# ATTint_SOMO-4D.net
KiCad netlist of a schematic drawn in EAGLE
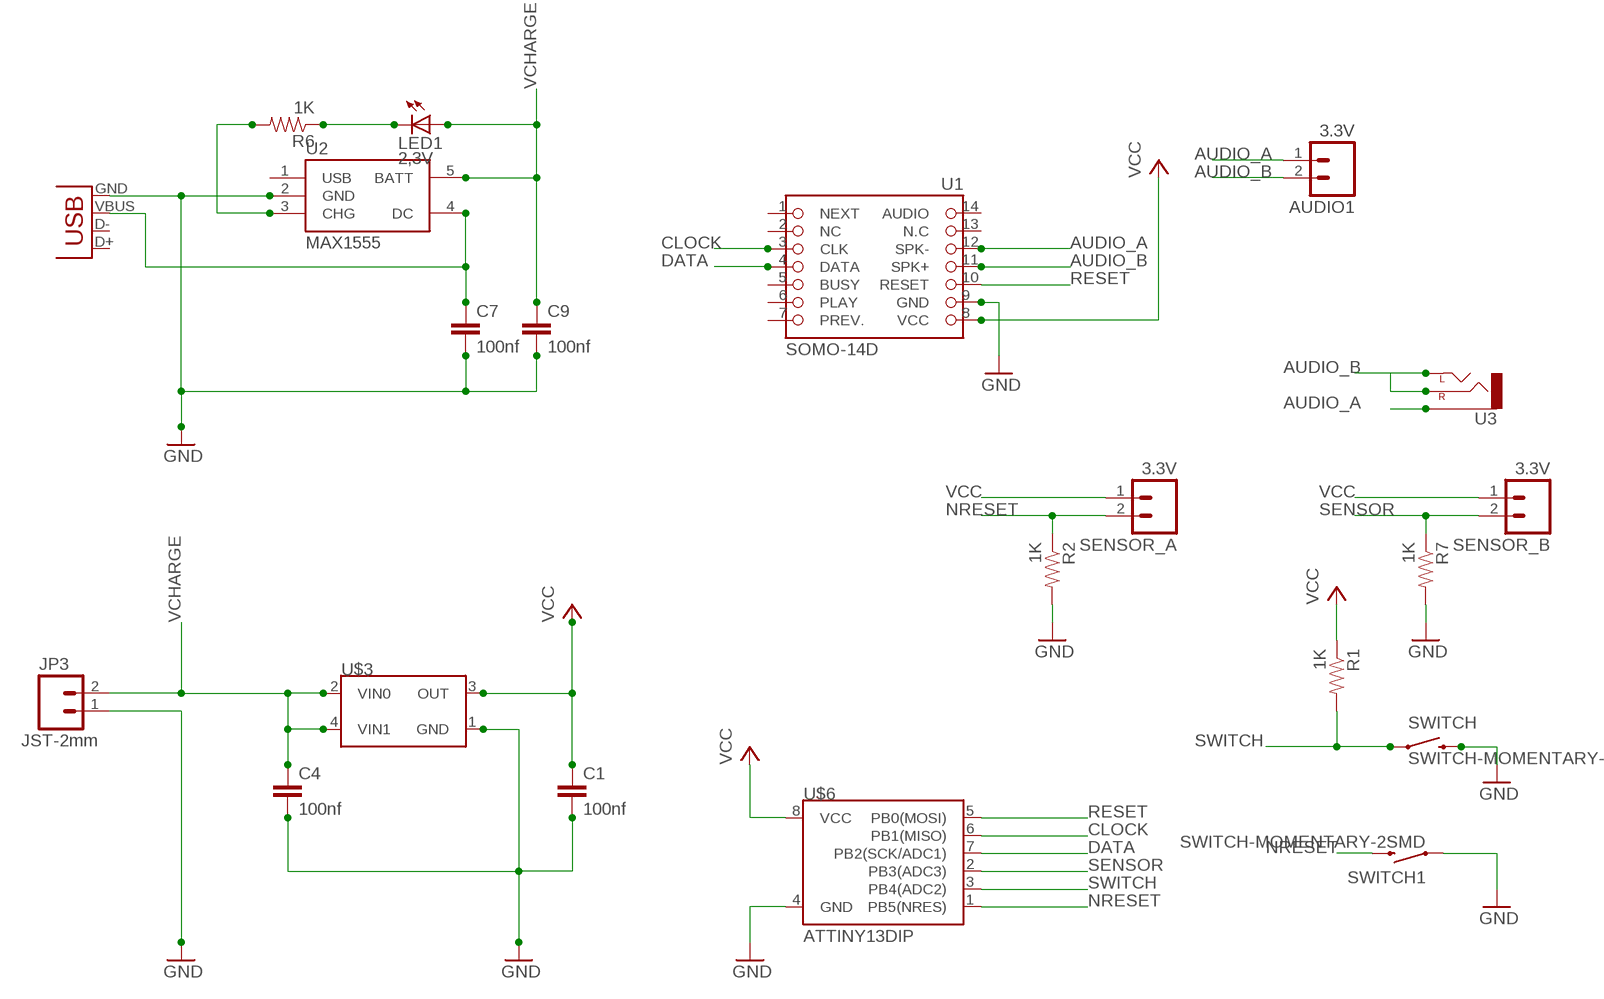
[diagram p0: schematic, sheet 1]

(export (version "E")
  (design (tool "Eeschema 10.0.6"))
  (components
    (comp (ref "AUDIO1")
      (value "3.3V")
      (footprint "eagle-import:1X02_LOCK_LONGPADS")
      (libsource (lib "eagle-import") (part "M02LOCK_LONGPADS"))
    )
    (comp (ref "C1")
      (value "100nf")
      (footprint "eagle-import:0805")
      (libsource (lib "eagle-import") (part "CAP0805"))
    )
    (comp (ref "C4")
      (value "100nf")
      (footprint "eagle-import:0805")
      (libsource (lib "eagle-import") (part "CAP0805"))
    )
    (comp (ref "C7")
      (value "100nf")
      (footprint "eagle-import:0805")
      (libsource (lib "eagle-import") (part "CAP0805"))
    )
    (comp (ref "C9")
      (value "100nf")
      (footprint "eagle-import:0805")
      (libsource (lib "eagle-import") (part "CAP0805"))
    )
    (comp (ref "JP3")
      (value "JST-2mm")
      (footprint "eagle-import:JST-2-SMD")
      (libsource (lib "eagle-import") (part "M02-JST-2MM-SMT"))
    )
    (comp (ref "LED1")
      (value "2,3V")
      (footprint "eagle-import:CHIP-LED0805")
      (libsource (lib "eagle-import") (part "LEDCHIP-LED0805"))
    )
    (comp (ref "R1")
      (value "1K")
      (footprint "eagle-import:0805")
      (libsource (lib "eagle-import") (part "RESISTOR"))
    )
    (comp (ref "R2")
      (value "1K")
      (footprint "eagle-import:0805")
      (libsource (lib "eagle-import") (part "RESISTOR"))
    )
    (comp (ref "R6")
      (value "1K")
      (footprint "eagle-import:0805")
      (libsource (lib "eagle-import") (part "RESISTOR"))
    )
    (comp (ref "R7")
      (value "1K")
      (footprint "eagle-import:0805")
      (libsource (lib "eagle-import") (part "RESISTOR"))
    )
    (comp (ref "SENSOR_A")
      (value "3.3V")
      (footprint "eagle-import:1X02_LOCK_LONGPADS")
      (libsource (lib "eagle-import") (part "charles_M02LOCK_LONGPADS"))
    )
    (comp (ref "SENSOR_B")
      (value "3.3V")
      (footprint "eagle-import:1X02_LOCK_LONGPADS")
      (libsource (lib "eagle-import") (part "charles_M02LOCK_LONGPADS"))
    )
    (comp (ref "SWITCH")
      (value "SWITCH-MOMENTARY-2")
      (footprint "eagle-import:TACTILE_SWITCH_TALL")
      (libsource (lib "eagle-import") (part "SWITCH-MOMENTARY-2"))
    )
    (comp (ref "SWITCH1")
      (value "SWITCH-MOMENTARY-2SMD")
      (footprint "eagle-import:TACTILE_SWITCH_SMD")
      (libsource (lib "eagle-import") (part "SWITCH-MOMENTARY-2SMD"))
    )
    (comp (ref "U$3")
      (value "MCP1703")
      (footprint "eagle-import:SOT-89")
      (libsource (lib "eagle-import") (part "MCP1703"))
    )
    (comp (ref "U$6")
      (value "ATTINY13DIP")
      (footprint "eagle-import:DIP08")
      (libsource (lib "eagle-import") (part "ATTINY13DIP"))
    )
    (comp (ref "U1")
      (value "SOMO-14D")
      (footprint "eagle-import:SOMO-14D")
      (libsource (lib "eagle-import") (part "SOMO-14D"))
    )
    (comp (ref "U2")
      (value "MAX1555")
      (footprint "eagle-import:SOT23-5")
      (libsource (lib "eagle-import") (part "MAX1555"))
    )
    (comp (ref "U3")
      (value "AUDIO-JACKSMD2")
      (footprint "eagle-import:AUDIO-JACK-3.5MM-SMD")
      (libsource (lib "eagle-import") (part "AUDIO-JACKSMD2"))
    )
    (comp (ref "X3")
      (value "USB-SMD-NS")
      (footprint "eagle-import:USB-MINIB-NOSTOP")
      (libsource (lib "eagle-import") (part "USB-SMD-NS"))
    )
  )
  (nets
    (net (code "1") (name "/AUDIO_A") (class "Default")
      (node (ref "AUDIO1") (pin "1") (pinfunction "1_1") (pintype "passive"))
      (node (ref "U1") (pin "12") (pinfunction "SPK-_12") (pintype "output"))
      (node (ref "U3") (pin "SLEEVE") (pinfunction "SLEEVE_SLEEVE") (pintype "bidirectional"))
    )
    (net (code "2") (name "/AUDIO_B") (class "Default")
      (node (ref "AUDIO1") (pin "2") (pinfunction "2_2") (pintype "passive"))
      (node (ref "U1") (pin "11") (pinfunction "SPK+_11") (pintype "output"))
      (node (ref "U3") (pin "RING") (pinfunction "RIGHT_RING") (pintype "bidirectional"))
      (node (ref "U3") (pin "TIP") (pinfunction "LEFT_TIP") (pintype "bidirectional"))
    )
    (net (code "3") (name "/CLOCK") (class "Default")
      (node (ref "U$6") (pin "6") (pinfunction "PB1(MISO)_6") (pintype "bidirectional"))
      (node (ref "U1") (pin "3") (pinfunction "CLK_3") (pintype "input"))
    )
    (net (code "4") (name "/DATA") (class "Default")
      (node (ref "U$6") (pin "7") (pinfunction "PB2(SCK/ADC1)_7") (pintype "bidirectional"))
      (node (ref "U1") (pin "4") (pinfunction "DATA_4") (pintype "input"))
    )
    (net (code "5") (name "/NRESET") (class "Default")
      (node (ref "R2") (pin "1") (pinfunction "1_1") (pintype "passive"))
      (node (ref "SENSOR_A") (pin "2") (pinfunction "2_2") (pintype "passive"))
      (node (ref "SWITCH1") (pin "3") (pinfunction "2_3") (pintype "passive"))
      (node (ref "U$6") (pin "1") (pinfunction "PB5(NRES)_1") (pintype "bidirectional"))
    )
    (net (code "6") (name "/RESET") (class "Default")
      (node (ref "U$6") (pin "5") (pinfunction "PB0(MOSI)_5") (pintype "bidirectional"))
      (node (ref "U1") (pin "10") (pinfunction "RESET_10") (pintype "power_in"))
    )
    (net (code "7") (name "/SENSOR") (class "Default")
      (node (ref "R7") (pin "1") (pinfunction "1_1") (pintype "passive"))
      (node (ref "SENSOR_B") (pin "2") (pinfunction "2_2") (pintype "passive"))
      (node (ref "U$6") (pin "2") (pinfunction "PB3(ADC3)_2") (pintype "bidirectional"))
    )
    (net (code "8") (name "/SWITCH") (class "Default")
      (node (ref "R1") (pin "2") (pinfunction "2_2") (pintype "passive"))
      (node (ref "SWITCH") (pin "A2") (pinfunction "1_A2") (pintype "passive"))
      (node (ref "U$6") (pin "3") (pinfunction "PB4(ADC2)_3") (pintype "bidirectional"))
    )
    (net (code "9") (name "/VCHARGE") (class "Default")
      (node (ref "C4") (pin "1") (pinfunction "1_1") (pintype "passive"))
      (node (ref "C9") (pin "1") (pinfunction "1_1") (pintype "passive"))
      (node (ref "JP3") (pin "2") (pinfunction "2_2") (pintype "passive"))
      (node (ref "LED1") (pin "A") (pinfunction "A_A") (pintype "passive"))
      (node (ref "U$3") (pin "2") (pinfunction "VIN0_2") (pintype "bidirectional"))
      (node (ref "U$3") (pin "4") (pinfunction "VIN1_4") (pintype "bidirectional"))
      (node (ref "U2") (pin "5") (pinfunction "BATT_5") (pintype "bidirectional"))
    )
    (net (code "10") (name "GND") (class "Default")
      (node (ref "C1") (pin "2") (pinfunction "2_2") (pintype "passive"))
      (node (ref "C4") (pin "2") (pinfunction "2_2") (pintype "passive"))
      (node (ref "C7") (pin "2") (pinfunction "2_2") (pintype "passive"))
      (node (ref "C9") (pin "2") (pinfunction "2_2") (pintype "passive"))
      (node (ref "JP3") (pin "1") (pinfunction "1_1") (pintype "passive"))
      (node (ref "R2") (pin "2") (pinfunction "2_2") (pintype "passive"))
      (node (ref "R7") (pin "2") (pinfunction "2_2") (pintype "passive"))
      (node (ref "SWITCH") (pin "B2") (pinfunction "2_B2") (pintype "passive"))
      (node (ref "SWITCH1") (pin "1") (pinfunction "1_1") (pintype "passive"))
      (node (ref "U$3") (pin "1") (pinfunction "GND_1") (pintype "bidirectional"))
      (node (ref "U$6") (pin "4") (pinfunction "GND_4") (pintype "bidirectional"))
      (node (ref "U1") (pin "9") (pinfunction "GND_9") (pintype "input"))
      (node (ref "U2") (pin "2") (pinfunction "GND_2") (pintype "bidirectional"))
      (node (ref "X3") (pin "GND") (pinfunction "GND_GND") (pintype "bidirectional"))
    )
    (net (code "11") (name "Net-(LED1-PadC)") (class "Default")
      (node (ref "LED1") (pin "C") (pinfunction "C_C") (pintype "passive"))
      (node (ref "R6") (pin "1") (pinfunction "1_1") (pintype "passive"))
    )
    (net (code "12") (name "Net-(U2-CHG)") (class "Default")
      (node (ref "R6") (pin "2") (pinfunction "2_2") (pintype "passive"))
      (node (ref "U2") (pin "3") (pinfunction "CHG_3") (pintype "bidirectional"))
    )
    (net (code "13") (name "Net-(U2-DC)") (class "Default")
      (node (ref "C7") (pin "1") (pinfunction "1_1") (pintype "passive"))
      (node (ref "U2") (pin "4") (pinfunction "DC_4") (pintype "bidirectional"))
      (node (ref "X3") (pin "VBUS") (pinfunction "VBUS_VBUS") (pintype "bidirectional"))
    )
    (net (code "14") (name "VCC") (class "Default")
      (node (ref "C1") (pin "1") (pinfunction "1_1") (pintype "passive"))
      (node (ref "R1") (pin "1") (pinfunction "1_1") (pintype "passive"))
      (node (ref "SENSOR_A") (pin "1") (pinfunction "1_1") (pintype "passive"))
      (node (ref "SENSOR_B") (pin "1") (pinfunction "1_1") (pintype "passive"))
      (node (ref "U$3") (pin "3") (pinfunction "OUT_3") (pintype "bidirectional"))
      (node (ref "U$6") (pin "8") (pinfunction "VCC_8") (pintype "bidirectional"))
      (node (ref "U1") (pin "8") (pinfunction "VCC_8") (pintype "power_in"))
    )
    (net (code "15") (name "unconnected-(U1-AUDIO-Pad14)") (class "Default")
      (node (ref "U1") (pin "14") (pinfunction "AUDIO_14") (pintype "output"))
    )
    (net (code "16") (name "unconnected-(U1-BUSY-Pad5)") (class "Default")
      (node (ref "U1") (pin "5") (pinfunction "BUSY_5") (pintype "output"))
    )
    (net (code "17") (name "unconnected-(U1-N.C-Pad13)") (class "Default")
      (node (ref "U1") (pin "13") (pinfunction "N.C_13") (pintype "no_connect"))
    )
    (net (code "18") (name "unconnected-(U1-NC-Pad2)") (class "Default")
      (node (ref "U1") (pin "2") (pinfunction "NC_2") (pintype "no_connect"))
    )
    (net (code "19") (name "unconnected-(U1-NEXT-Pad1)") (class "Default")
      (node (ref "U1") (pin "1") (pinfunction "NEXT_1") (pintype "input"))
    )
    (net (code "20") (name "unconnected-(U1-PLAY-Pad6)") (class "Default")
      (node (ref "U1") (pin "6") (pinfunction "PLAY_6") (pintype "input"))
    )
    (net (code "21") (name "unconnected-(U1-PREV.-Pad7)") (class "Default")
      (node (ref "U1") (pin "7") (pinfunction "PREV._7") (pintype "input"))
    )
    (net (code "22") (name "unconnected-(U2-USB-Pad1)") (class "Default")
      (node (ref "U2") (pin "1") (pinfunction "USB_1") (pintype "bidirectional"))
    )
    (net (code "23") (name "unconnected-(X3-PadD+)") (class "Default")
      (node (ref "X3") (pin "D+") (pinfunction "D+_D+") (pintype "bidirectional"))
    )
    (net (code "24") (name "unconnected-(X3-PadD-)") (class "Default")
      (node (ref "X3") (pin "D-") (pinfunction "D-_D-") (pintype "bidirectional"))
    )
  )
)
